# Clock.net
KiCad netlist of a schematic drawn in Altium Designer
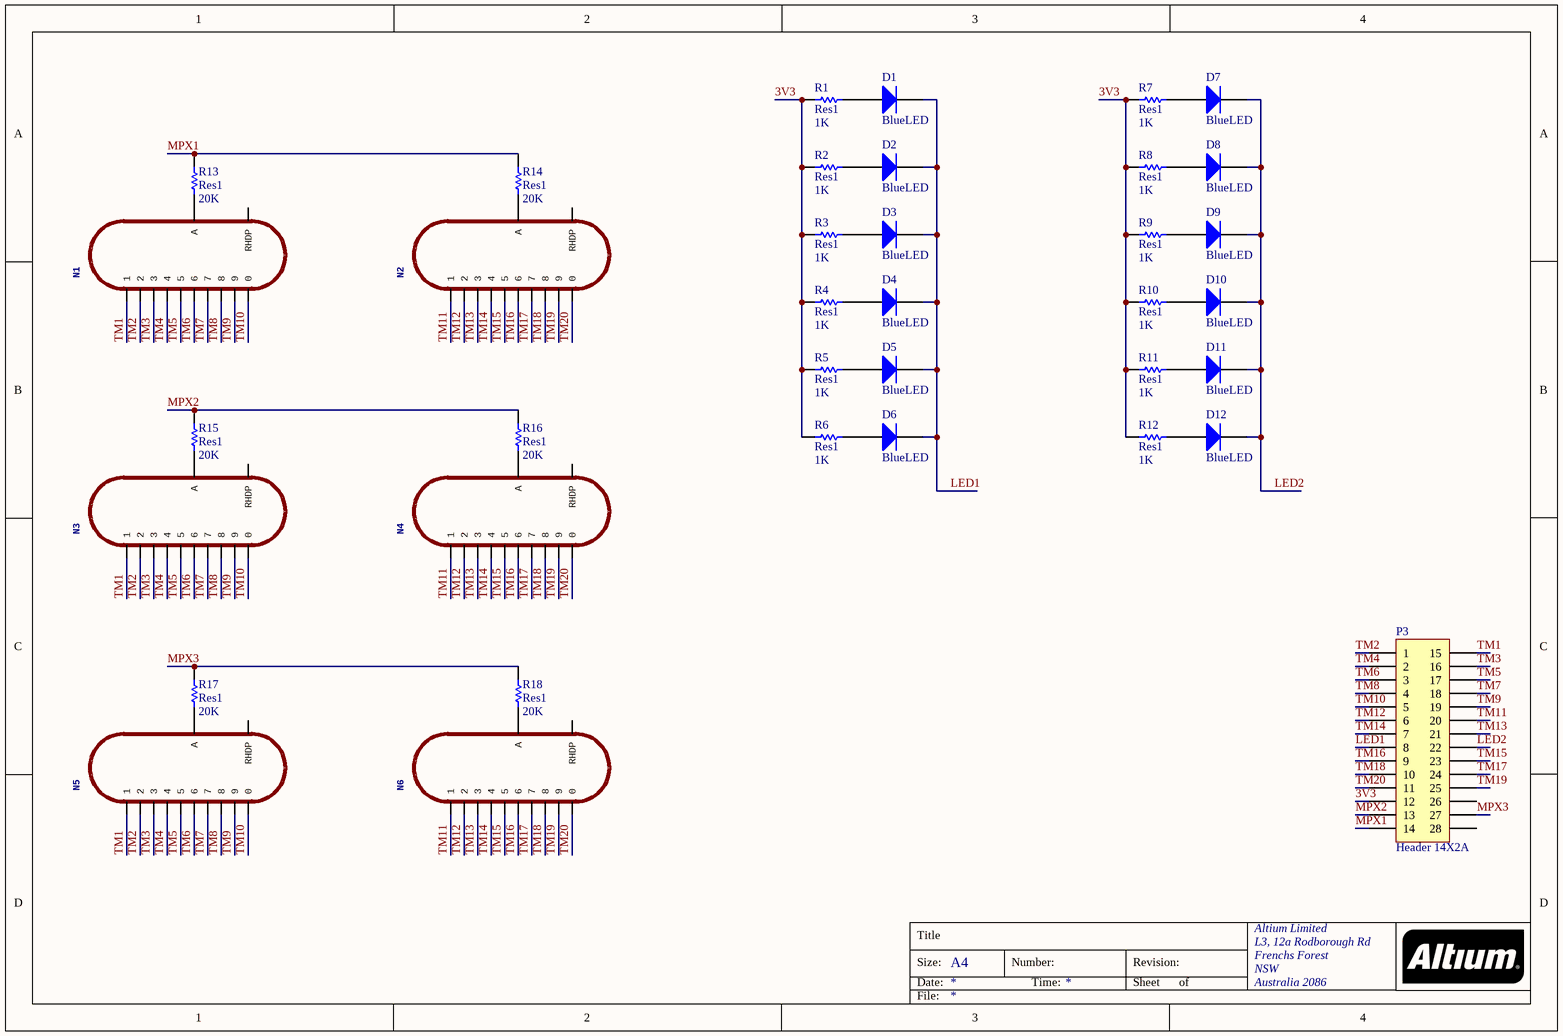
[diagram p0: Clock.SchDoc]

(export (version "E")
  (design (tool "Eeschema 10.0.6"))
  (components
    (comp (ref "D1")
      (value "BlueLED")
      (footprint "1608[0603]")
      (description "Default Diode")
      (fields (field (name "PUBLISHER") "Altium Limited"))
      (libsource (lib "Miscellaneous Devices") (part "Diode"))
    )
    (comp (ref "D2")
      (value "BlueLED")
      (footprint "1608[0603]")
      (description "Default Diode")
      (fields (field (name "PUBLISHER") "Altium Limited"))
      (libsource (lib "Miscellaneous Devices") (part "Diode"))
    )
    (comp (ref "D3")
      (value "BlueLED")
      (footprint "1608[0603]")
      (description "Default Diode")
      (fields (field (name "PUBLISHER") "Altium Limited"))
      (libsource (lib "Miscellaneous Devices") (part "Diode"))
    )
    (comp (ref "D4")
      (value "BlueLED")
      (footprint "1608[0603]")
      (description "Default Diode")
      (fields (field (name "PUBLISHER") "Altium Limited"))
      (libsource (lib "Miscellaneous Devices") (part "Diode"))
    )
    (comp (ref "D5")
      (value "BlueLED")
      (footprint "1608[0603]")
      (description "Default Diode")
      (fields (field (name "PUBLISHER") "Altium Limited"))
      (libsource (lib "Miscellaneous Devices") (part "Diode"))
    )
    (comp (ref "D6")
      (value "BlueLED")
      (footprint "1608[0603]")
      (description "Default Diode")
      (fields (field (name "PUBLISHER") "Altium Limited"))
      (libsource (lib "Miscellaneous Devices") (part "Diode"))
    )
    (comp (ref "D7")
      (value "BlueLED")
      (footprint "1608[0603]")
      (description "Default Diode")
      (fields (field (name "PUBLISHER") "Altium Limited"))
      (libsource (lib "Miscellaneous Devices") (part "Diode"))
    )
    (comp (ref "D8")
      (value "BlueLED")
      (footprint "1608[0603]")
      (description "Default Diode")
      (fields (field (name "PUBLISHER") "Altium Limited"))
      (libsource (lib "Miscellaneous Devices") (part "Diode"))
    )
    (comp (ref "D9")
      (value "BlueLED")
      (footprint "1608[0603]")
      (description "Default Diode")
      (fields (field (name "PUBLISHER") "Altium Limited"))
      (libsource (lib "Miscellaneous Devices") (part "Diode"))
    )
    (comp (ref "D10")
      (value "BlueLED")
      (footprint "1608[0603]")
      (description "Default Diode")
      (fields (field (name "PUBLISHER") "Altium Limited"))
      (libsource (lib "Miscellaneous Devices") (part "Diode"))
    )
    (comp (ref "D11")
      (value "BlueLED")
      (footprint "1608[0603]")
      (description "Default Diode")
      (fields (field (name "PUBLISHER") "Altium Limited"))
      (libsource (lib "Miscellaneous Devices") (part "Diode"))
    )
    (comp (ref "D12")
      (value "BlueLED")
      (footprint "1608[0603]")
      (description "Default Diode")
      (fields (field (name "PUBLISHER") "Altium Limited"))
      (libsource (lib "Miscellaneous Devices") (part "Diode"))
    )
    (comp (ref "N1")
      (value "IN-8-2: medium numeric frontview nixie tube")
      (footprint "IN-8-2")
      (fields (field (name "LIBRARYNAME") "nixie-tubes"))
      (libsource (lib "nixie-tubes") (part "IN-8-2"))
    )
    (comp (ref "N2")
      (value "IN-8-2: medium numeric frontview nixie tube")
      (footprint "IN-8-2")
      (fields (field (name "LIBRARYNAME") "nixie-tubes"))
      (libsource (lib "nixie-tubes") (part "IN-8-2"))
    )
    (comp (ref "N3")
      (value "IN-8-2: medium numeric frontview nixie tube")
      (footprint "IN-8-2")
      (fields (field (name "LIBRARYNAME") "nixie-tubes"))
      (libsource (lib "nixie-tubes") (part "IN-8-2"))
    )
    (comp (ref "N4")
      (value "IN-8-2: medium numeric frontview nixie tube")
      (footprint "IN-8-2")
      (fields (field (name "LIBRARYNAME") "nixie-tubes"))
      (libsource (lib "nixie-tubes") (part "IN-8-2"))
    )
    (comp (ref "N5")
      (value "IN-8-2: medium numeric frontview nixie tube")
      (footprint "IN-8-2")
      (fields (field (name "LIBRARYNAME") "nixie-tubes"))
      (libsource (lib "nixie-tubes") (part "IN-8-2"))
    )
    (comp (ref "N6")
      (value "IN-8-2: medium numeric frontview nixie tube")
      (footprint "IN-8-2")
      (fields (field (name "LIBRARYNAME") "nixie-tubes"))
      (libsource (lib "nixie-tubes") (part "IN-8-2"))
    )
    (comp (ref "P3")
      (value "Header 14X2A")
      (footprint "HDR2X14_CEN")
      (description "Header, 14-Pin, Dual row")
      (fields (field (name "PUBLISHER") "Altium Limited"))
      (libsource (lib "Miscellaneous Connectors") (part "Header 14X2A"))
    )
    (comp (ref "R1")
      (value "Res1")
      (footprint "1608[0603]")
      (description "Resistor")
      (fields (field (name "ALTIUM_VALUE") "1K") (field (name "PUBLISHER") "Altium Limited"))
      (libsource (lib "Miscellaneous Devices") (part "Res1"))
    )
    (comp (ref "R2")
      (value "Res1")
      (footprint "1608[0603]")
      (description "Resistor")
      (fields (field (name "ALTIUM_VALUE") "1K") (field (name "PUBLISHER") "Altium Limited"))
      (libsource (lib "Miscellaneous Devices") (part "Res1"))
    )
    (comp (ref "R3")
      (value "Res1")
      (footprint "1608[0603]")
      (description "Resistor")
      (fields (field (name "ALTIUM_VALUE") "1K") (field (name "PUBLISHER") "Altium Limited"))
      (libsource (lib "Miscellaneous Devices") (part "Res1"))
    )
    (comp (ref "R4")
      (value "Res1")
      (footprint "1608[0603]")
      (description "Resistor")
      (fields (field (name "ALTIUM_VALUE") "1K") (field (name "PUBLISHER") "Altium Limited"))
      (libsource (lib "Miscellaneous Devices") (part "Res1"))
    )
    (comp (ref "R5")
      (value "Res1")
      (footprint "1608[0603]")
      (description "Resistor")
      (fields (field (name "ALTIUM_VALUE") "1K") (field (name "PUBLISHER") "Altium Limited"))
      (libsource (lib "Miscellaneous Devices") (part "Res1"))
    )
    (comp (ref "R6")
      (value "Res1")
      (footprint "1608[0603]")
      (description "Resistor")
      (fields (field (name "ALTIUM_VALUE") "1K") (field (name "PUBLISHER") "Altium Limited"))
      (libsource (lib "Miscellaneous Devices") (part "Res1"))
    )
    (comp (ref "R7")
      (value "Res1")
      (footprint "1608[0603]")
      (description "Resistor")
      (fields (field (name "ALTIUM_VALUE") "1K") (field (name "PUBLISHER") "Altium Limited"))
      (libsource (lib "Miscellaneous Devices") (part "Res1"))
    )
    (comp (ref "R8")
      (value "Res1")
      (footprint "1608[0603]")
      (description "Resistor")
      (fields (field (name "ALTIUM_VALUE") "1K") (field (name "PUBLISHER") "Altium Limited"))
      (libsource (lib "Miscellaneous Devices") (part "Res1"))
    )
    (comp (ref "R9")
      (value "Res1")
      (footprint "1608[0603]")
      (description "Resistor")
      (fields (field (name "ALTIUM_VALUE") "1K") (field (name "PUBLISHER") "Altium Limited"))
      (libsource (lib "Miscellaneous Devices") (part "Res1"))
    )
    (comp (ref "R10")
      (value "Res1")
      (footprint "1608[0603]")
      (description "Resistor")
      (fields (field (name "ALTIUM_VALUE") "1K") (field (name "PUBLISHER") "Altium Limited"))
      (libsource (lib "Miscellaneous Devices") (part "Res1"))
    )
    (comp (ref "R11")
      (value "Res1")
      (footprint "1608[0603]")
      (description "Resistor")
      (fields (field (name "ALTIUM_VALUE") "1K") (field (name "PUBLISHER") "Altium Limited"))
      (libsource (lib "Miscellaneous Devices") (part "Res1"))
    )
    (comp (ref "R12")
      (value "Res1")
      (footprint "1608[0603]")
      (description "Resistor")
      (fields (field (name "ALTIUM_VALUE") "1K") (field (name "PUBLISHER") "Altium Limited"))
      (libsource (lib "Miscellaneous Devices") (part "Res1"))
    )
    (comp (ref "R13")
      (value "Res1")
      (footprint "6-0805_M")
      (description "Resistor")
      (fields (field (name "ALTIUM_VALUE") "20K") (field (name "PUBLISHER") "Altium Limited"))
      (libsource (lib "Miscellaneous Devices") (part "Res1"))
    )
    (comp (ref "R14")
      (value "Res1")
      (footprint "6-0805_M")
      (description "Resistor")
      (fields (field (name "ALTIUM_VALUE") "20K") (field (name "PUBLISHER") "Altium Limited"))
      (libsource (lib "Miscellaneous Devices") (part "Res1"))
    )
    (comp (ref "R15")
      (value "Res1")
      (footprint "6-0805_M")
      (description "Resistor")
      (fields (field (name "ALTIUM_VALUE") "20K") (field (name "PUBLISHER") "Altium Limited"))
      (libsource (lib "Miscellaneous Devices") (part "Res1"))
    )
    (comp (ref "R16")
      (value "Res1")
      (footprint "6-0805_M")
      (description "Resistor")
      (fields (field (name "ALTIUM_VALUE") "20K") (field (name "PUBLISHER") "Altium Limited"))
      (libsource (lib "Miscellaneous Devices") (part "Res1"))
    )
    (comp (ref "R17")
      (value "Res1")
      (footprint "6-0805_M")
      (description "Resistor")
      (fields (field (name "ALTIUM_VALUE") "20K") (field (name "PUBLISHER") "Altium Limited"))
      (libsource (lib "Miscellaneous Devices") (part "Res1"))
    )
    (comp (ref "R18")
      (value "Res1")
      (footprint "6-0805_M")
      (description "Resistor")
      (fields (field (name "ALTIUM_VALUE") "20K") (field (name "PUBLISHER") "Altium Limited"))
      (libsource (lib "Miscellaneous Devices") (part "Res1"))
    )
  )
  (nets
    (net (code "1") (name "/3V3") (class "Default")
      (node (ref "P3") (pin "12") (pinfunction "12_12") (pintype "passive"))
      (node (ref "R1") (pin "1") (pinfunction "1_1") (pintype "passive"))
      (node (ref "R10") (pin "1") (pinfunction "1_1") (pintype "passive"))
      (node (ref "R11") (pin "1") (pinfunction "1_1") (pintype "passive"))
      (node (ref "R12") (pin "1") (pinfunction "1_1") (pintype "passive"))
      (node (ref "R2") (pin "1") (pinfunction "1_1") (pintype "passive"))
      (node (ref "R3") (pin "1") (pinfunction "1_1") (pintype "passive"))
      (node (ref "R4") (pin "1") (pinfunction "1_1") (pintype "passive"))
      (node (ref "R5") (pin "1") (pinfunction "1_1") (pintype "passive"))
      (node (ref "R6") (pin "1") (pinfunction "1_1") (pintype "passive"))
      (node (ref "R7") (pin "1") (pinfunction "1_1") (pintype "passive"))
      (node (ref "R8") (pin "1") (pinfunction "1_1") (pintype "passive"))
      (node (ref "R9") (pin "1") (pinfunction "1_1") (pintype "passive"))
    )
    (net (code "2") (name "/LED1") (class "Default")
      (node (ref "D1") (pin "2") (pinfunction "K_2") (pintype "passive"))
      (node (ref "D2") (pin "2") (pinfunction "K_2") (pintype "passive"))
      (node (ref "D3") (pin "2") (pinfunction "K_2") (pintype "passive"))
      (node (ref "D4") (pin "2") (pinfunction "K_2") (pintype "passive"))
      (node (ref "D5") (pin "2") (pinfunction "K_2") (pintype "passive"))
      (node (ref "D6") (pin "2") (pinfunction "K_2") (pintype "passive"))
      (node (ref "P3") (pin "8") (pinfunction "8_8") (pintype "passive"))
    )
    (net (code "3") (name "/LED2") (class "Default")
      (node (ref "D10") (pin "2") (pinfunction "K_2") (pintype "passive"))
      (node (ref "D11") (pin "2") (pinfunction "K_2") (pintype "passive"))
      (node (ref "D12") (pin "2") (pinfunction "K_2") (pintype "passive"))
      (node (ref "D7") (pin "2") (pinfunction "K_2") (pintype "passive"))
      (node (ref "D8") (pin "2") (pinfunction "K_2") (pintype "passive"))
      (node (ref "D9") (pin "2") (pinfunction "K_2") (pintype "passive"))
      (node (ref "P3") (pin "22") (pinfunction "22_22") (pintype "passive"))
    )
    (net (code "4") (name "/MPX1") (class "Default")
      (node (ref "P3") (pin "14") (pinfunction "14_14") (pintype "passive"))
      (node (ref "R13") (pin "2") (pinfunction "2_2") (pintype "passive"))
      (node (ref "R14") (pin "2") (pinfunction "2_2") (pintype "passive"))
    )
    (net (code "5") (name "/MPX2") (class "Default")
      (node (ref "P3") (pin "13") (pinfunction "13_13") (pintype "passive"))
      (node (ref "R15") (pin "2") (pinfunction "2_2") (pintype "passive"))
      (node (ref "R16") (pin "2") (pinfunction "2_2") (pintype "passive"))
    )
    (net (code "6") (name "/MPX3") (class "Default")
      (node (ref "P3") (pin "27") (pinfunction "27_27") (pintype "passive"))
      (node (ref "R17") (pin "2") (pinfunction "2_2") (pintype "passive"))
      (node (ref "R18") (pin "2") (pinfunction "2_2") (pintype "passive"))
    )
    (net (code "7") (name "/TM1") (class "Default")
      (node (ref "N1") (pin "1") (pinfunction "1_1") (pintype "passive"))
      (node (ref "N3") (pin "1") (pinfunction "1_1") (pintype "passive"))
      (node (ref "N5") (pin "1") (pinfunction "1_1") (pintype "passive"))
      (node (ref "P3") (pin "15") (pinfunction "15_15") (pintype "passive"))
    )
    (net (code "8") (name "/TM2") (class "Default")
      (node (ref "N1") (pin "2") (pinfunction "2_2") (pintype "passive"))
      (node (ref "N3") (pin "2") (pinfunction "2_2") (pintype "passive"))
      (node (ref "N5") (pin "2") (pinfunction "2_2") (pintype "passive"))
      (node (ref "P3") (pin "1") (pinfunction "1_1") (pintype "passive"))
    )
    (net (code "9") (name "/TM3") (class "Default")
      (node (ref "N1") (pin "3") (pinfunction "3_3") (pintype "passive"))
      (node (ref "N3") (pin "3") (pinfunction "3_3") (pintype "passive"))
      (node (ref "N5") (pin "3") (pinfunction "3_3") (pintype "passive"))
      (node (ref "P3") (pin "16") (pinfunction "16_16") (pintype "passive"))
    )
    (net (code "10") (name "/TM4") (class "Default")
      (node (ref "N1") (pin "4") (pinfunction "4_4") (pintype "passive"))
      (node (ref "N3") (pin "4") (pinfunction "4_4") (pintype "passive"))
      (node (ref "N5") (pin "4") (pinfunction "4_4") (pintype "passive"))
      (node (ref "P3") (pin "2") (pinfunction "2_2") (pintype "passive"))
    )
    (net (code "11") (name "/TM5") (class "Default")
      (node (ref "N1") (pin "5") (pinfunction "5_5") (pintype "passive"))
      (node (ref "N3") (pin "5") (pinfunction "5_5") (pintype "passive"))
      (node (ref "N5") (pin "5") (pinfunction "5_5") (pintype "passive"))
      (node (ref "P3") (pin "17") (pinfunction "17_17") (pintype "passive"))
    )
    (net (code "12") (name "/TM6") (class "Default")
      (node (ref "N1") (pin "6") (pinfunction "6_6") (pintype "passive"))
      (node (ref "N3") (pin "6") (pinfunction "6_6") (pintype "passive"))
      (node (ref "N5") (pin "6") (pinfunction "6_6") (pintype "passive"))
      (node (ref "P3") (pin "3") (pinfunction "3_3") (pintype "passive"))
    )
    (net (code "13") (name "/TM7") (class "Default")
      (node (ref "N1") (pin "7") (pinfunction "7_7") (pintype "passive"))
      (node (ref "N3") (pin "7") (pinfunction "7_7") (pintype "passive"))
      (node (ref "N5") (pin "7") (pinfunction "7_7") (pintype "passive"))
      (node (ref "P3") (pin "18") (pinfunction "18_18") (pintype "passive"))
    )
    (net (code "14") (name "/TM8") (class "Default")
      (node (ref "N1") (pin "8") (pinfunction "8_8") (pintype "passive"))
      (node (ref "N3") (pin "8") (pinfunction "8_8") (pintype "passive"))
      (node (ref "N5") (pin "8") (pinfunction "8_8") (pintype "passive"))
      (node (ref "P3") (pin "4") (pinfunction "4_4") (pintype "passive"))
    )
    (net (code "15") (name "/TM9") (class "Default")
      (node (ref "N1") (pin "9") (pinfunction "9_9") (pintype "passive"))
      (node (ref "N3") (pin "9") (pinfunction "9_9") (pintype "passive"))
      (node (ref "N5") (pin "9") (pinfunction "9_9") (pintype "passive"))
      (node (ref "P3") (pin "19") (pinfunction "19_19") (pintype "passive"))
    )
    (net (code "16") (name "/TM10") (class "Default")
      (node (ref "N1") (pin "0") (pinfunction "0_0") (pintype "passive"))
      (node (ref "N3") (pin "0") (pinfunction "0_0") (pintype "passive"))
      (node (ref "N5") (pin "0") (pinfunction "0_0") (pintype "passive"))
      (node (ref "P3") (pin "5") (pinfunction "5_5") (pintype "passive"))
    )
    (net (code "17") (name "/TM11") (class "Default")
      (node (ref "N2") (pin "1") (pinfunction "1_1") (pintype "passive"))
      (node (ref "N4") (pin "1") (pinfunction "1_1") (pintype "passive"))
      (node (ref "N6") (pin "1") (pinfunction "1_1") (pintype "passive"))
      (node (ref "P3") (pin "20") (pinfunction "20_20") (pintype "passive"))
    )
    (net (code "18") (name "/TM12") (class "Default")
      (node (ref "N2") (pin "2") (pinfunction "2_2") (pintype "passive"))
      (node (ref "N4") (pin "2") (pinfunction "2_2") (pintype "passive"))
      (node (ref "N6") (pin "2") (pinfunction "2_2") (pintype "passive"))
      (node (ref "P3") (pin "6") (pinfunction "6_6") (pintype "passive"))
    )
    (net (code "19") (name "/TM13") (class "Default")
      (node (ref "N2") (pin "3") (pinfunction "3_3") (pintype "passive"))
      (node (ref "N4") (pin "3") (pinfunction "3_3") (pintype "passive"))
      (node (ref "N6") (pin "3") (pinfunction "3_3") (pintype "passive"))
      (node (ref "P3") (pin "21") (pinfunction "21_21") (pintype "passive"))
    )
    (net (code "20") (name "/TM14") (class "Default")
      (node (ref "N2") (pin "4") (pinfunction "4_4") (pintype "passive"))
      (node (ref "N4") (pin "4") (pinfunction "4_4") (pintype "passive"))
      (node (ref "N6") (pin "4") (pinfunction "4_4") (pintype "passive"))
      (node (ref "P3") (pin "7") (pinfunction "7_7") (pintype "passive"))
    )
    (net (code "21") (name "/TM15") (class "Default")
      (node (ref "N2") (pin "5") (pinfunction "5_5") (pintype "passive"))
      (node (ref "N4") (pin "5") (pinfunction "5_5") (pintype "passive"))
      (node (ref "N6") (pin "5") (pinfunction "5_5") (pintype "passive"))
      (node (ref "P3") (pin "23") (pinfunction "23_23") (pintype "passive"))
    )
    (net (code "22") (name "/TM16") (class "Default")
      (node (ref "N2") (pin "6") (pinfunction "6_6") (pintype "passive"))
      (node (ref "N4") (pin "6") (pinfunction "6_6") (pintype "passive"))
      (node (ref "N6") (pin "6") (pinfunction "6_6") (pintype "passive"))
      (node (ref "P3") (pin "9") (pinfunction "9_9") (pintype "passive"))
    )
    (net (code "23") (name "/TM17") (class "Default")
      (node (ref "N2") (pin "7") (pinfunction "7_7") (pintype "passive"))
      (node (ref "N4") (pin "7") (pinfunction "7_7") (pintype "passive"))
      (node (ref "N6") (pin "7") (pinfunction "7_7") (pintype "passive"))
      (node (ref "P3") (pin "24") (pinfunction "24_24") (pintype "passive"))
    )
    (net (code "24") (name "/TM18") (class "Default")
      (node (ref "N2") (pin "8") (pinfunction "8_8") (pintype "passive"))
      (node (ref "N4") (pin "8") (pinfunction "8_8") (pintype "passive"))
      (node (ref "N6") (pin "8") (pinfunction "8_8") (pintype "passive"))
      (node (ref "P3") (pin "10") (pinfunction "10_10") (pintype "passive"))
    )
    (net (code "25") (name "/TM19") (class "Default")
      (node (ref "N2") (pin "9") (pinfunction "9_9") (pintype "passive"))
      (node (ref "N4") (pin "9") (pinfunction "9_9") (pintype "passive"))
      (node (ref "N6") (pin "9") (pinfunction "9_9") (pintype "passive"))
      (node (ref "P3") (pin "25") (pinfunction "25_25") (pintype "passive"))
    )
    (net (code "26") (name "/TM20") (class "Default")
      (node (ref "N2") (pin "0") (pinfunction "0_0") (pintype "passive"))
      (node (ref "N4") (pin "0") (pinfunction "0_0") (pintype "passive"))
      (node (ref "N6") (pin "0") (pinfunction "0_0") (pintype "passive"))
      (node (ref "P3") (pin "11") (pinfunction "11_11") (pintype "passive"))
    )
    (net (code "27") (name "Net-(D1-A)") (class "Default")
      (node (ref "D1") (pin "1") (pinfunction "A_1") (pintype "passive"))
      (node (ref "R1") (pin "2") (pinfunction "2_2") (pintype "passive"))
    )
    (net (code "28") (name "Net-(D2-A)") (class "Default")
      (node (ref "D2") (pin "1") (pinfunction "A_1") (pintype "passive"))
      (node (ref "R2") (pin "2") (pinfunction "2_2") (pintype "passive"))
    )
    (net (code "29") (name "Net-(D3-A)") (class "Default")
      (node (ref "D3") (pin "1") (pinfunction "A_1") (pintype "passive"))
      (node (ref "R3") (pin "2") (pinfunction "2_2") (pintype "passive"))
    )
    (net (code "30") (name "Net-(D4-A)") (class "Default")
      (node (ref "D4") (pin "1") (pinfunction "A_1") (pintype "passive"))
      (node (ref "R4") (pin "2") (pinfunction "2_2") (pintype "passive"))
    )
    (net (code "31") (name "Net-(D5-A)") (class "Default")
      (node (ref "D5") (pin "1") (pinfunction "A_1") (pintype "passive"))
      (node (ref "R5") (pin "2") (pinfunction "2_2") (pintype "passive"))
    )
    (net (code "32") (name "Net-(D6-A)") (class "Default")
      (node (ref "D6") (pin "1") (pinfunction "A_1") (pintype "passive"))
      (node (ref "R6") (pin "2") (pinfunction "2_2") (pintype "passive"))
    )
    (net (code "33") (name "Net-(D7-A)") (class "Default")
      (node (ref "D7") (pin "1") (pinfunction "A_1") (pintype "passive"))
      (node (ref "R7") (pin "2") (pinfunction "2_2") (pintype "passive"))
    )
    (net (code "34") (name "Net-(D8-A)") (class "Default")
      (node (ref "D8") (pin "1") (pinfunction "A_1") (pintype "passive"))
      (node (ref "R8") (pin "2") (pinfunction "2_2") (pintype "passive"))
    )
    (net (code "35") (name "Net-(D9-A)") (class "Default")
      (node (ref "D9") (pin "1") (pinfunction "A_1") (pintype "passive"))
      (node (ref "R9") (pin "2") (pinfunction "2_2") (pintype "passive"))
    )
    (net (code "36") (name "Net-(D10-A)") (class "Default")
      (node (ref "D10") (pin "1") (pinfunction "A_1") (pintype "passive"))
      (node (ref "R10") (pin "2") (pinfunction "2_2") (pintype "passive"))
    )
    (net (code "37") (name "Net-(D11-A)") (class "Default")
      (node (ref "D11") (pin "1") (pinfunction "A_1") (pintype "passive"))
      (node (ref "R11") (pin "2") (pinfunction "2_2") (pintype "passive"))
    )
    (net (code "38") (name "Net-(D12-A)") (class "Default")
      (node (ref "D12") (pin "1") (pinfunction "A_1") (pintype "passive"))
      (node (ref "R12") (pin "2") (pinfunction "2_2") (pintype "passive"))
    )
    (net (code "39") (name "Net-(N1-PadA)") (class "Default")
      (node (ref "N1") (pin "A") (pinfunction "A_A") (pintype "passive"))
      (node (ref "R13") (pin "1") (pinfunction "1_1") (pintype "passive"))
    )
    (net (code "40") (name "Net-(N2-PadA)") (class "Default")
      (node (ref "N2") (pin "A") (pinfunction "A_A") (pintype "passive"))
      (node (ref "R14") (pin "1") (pinfunction "1_1") (pintype "passive"))
    )
    (net (code "41") (name "Net-(N3-PadA)") (class "Default")
      (node (ref "N3") (pin "A") (pinfunction "A_A") (pintype "passive"))
      (node (ref "R15") (pin "1") (pinfunction "1_1") (pintype "passive"))
    )
    (net (code "42") (name "Net-(N4-PadA)") (class "Default")
      (node (ref "N4") (pin "A") (pinfunction "A_A") (pintype "passive"))
      (node (ref "R16") (pin "1") (pinfunction "1_1") (pintype "passive"))
    )
    (net (code "43") (name "Net-(N5-PadA)") (class "Default")
      (node (ref "N5") (pin "A") (pinfunction "A_A") (pintype "passive"))
      (node (ref "R17") (pin "1") (pinfunction "1_1") (pintype "passive"))
    )
    (net (code "44") (name "Net-(N6-PadA)") (class "Default")
      (node (ref "N6") (pin "A") (pinfunction "A_A") (pintype "passive"))
      (node (ref "R18") (pin "1") (pinfunction "1_1") (pintype "passive"))
    )
    (net (code "45") (name "unconnected-(N1-RHDP-Pad.)") (class "Default")
      (node (ref "N1") (pin ".") (pinfunction "RHDP_.") (pintype "passive"))
    )
    (net (code "46") (name "unconnected-(N2-RHDP-Pad.)") (class "Default")
      (node (ref "N2") (pin ".") (pinfunction "RHDP_.") (pintype "passive"))
    )
    (net (code "47") (name "unconnected-(N3-RHDP-Pad.)") (class "Default")
      (node (ref "N3") (pin ".") (pinfunction "RHDP_.") (pintype "passive"))
    )
    (net (code "48") (name "unconnected-(N4-RHDP-Pad.)") (class "Default")
      (node (ref "N4") (pin ".") (pinfunction "RHDP_.") (pintype "passive"))
    )
    (net (code "49") (name "unconnected-(N5-RHDP-Pad.)") (class "Default")
      (node (ref "N5") (pin ".") (pinfunction "RHDP_.") (pintype "passive"))
    )
    (net (code "50") (name "unconnected-(N6-RHDP-Pad.)") (class "Default")
      (node (ref "N6") (pin ".") (pinfunction "RHDP_.") (pintype "passive"))
    )
    (net (code "51") (name "unconnected-(P3-Pad26)") (class "Default")
      (node (ref "P3") (pin "26") (pinfunction "26_26") (pintype "passive"))
    )
    (net (code "52") (name "unconnected-(P3-Pad28)") (class "Default")
      (node (ref "P3") (pin "28") (pinfunction "28_28") (pintype "passive"))
    )
  )
)
